# nrf51.net
KiCad netlist of a schematic drawn in Altium Designer
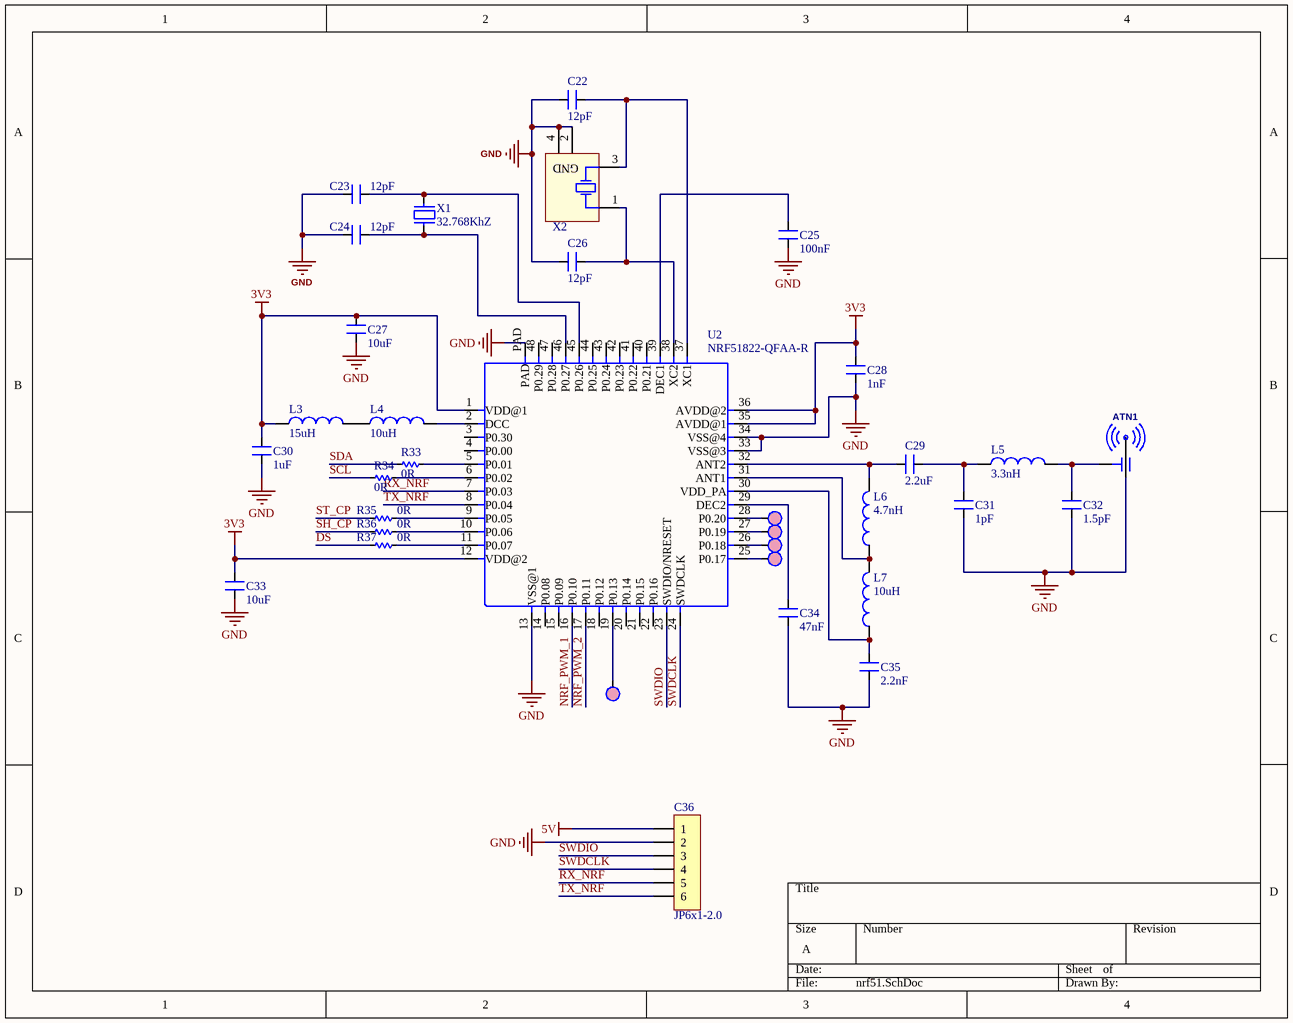
[diagram p0: nrf51.SchDoc]

(export (version "E")
  (design (tool "Eeschema 10.0.6"))
  (components
    (comp (ref "ATN1")
      (value "P-ANT")
      (footprint "Antenna 2G4")
      (libsource (lib "VitalSignal EcgPpg Board") (part "P-ANT"))
    )
    (comp (ref "C22")
      (value "12pF")
      (footprint "CN-SMD-0603")
      (description "Tu gom")
      (libsource (lib "LIBTanCN") (part "CN"))
    )
    (comp (ref "C23")
      (value "12pF")
      (footprint "CN-SMD-0603")
      (description "Tu gom")
      (libsource (lib "LIBTanCN") (part "CN"))
    )
    (comp (ref "C24")
      (value "12pF")
      (footprint "CN-SMD-0603")
      (description "Tu gom")
      (libsource (lib "LIBTanCN") (part "CN"))
    )
    (comp (ref "C25")
      (value "100nF")
      (footprint "CN-SMD-0603")
      (description "Tu gom")
      (libsource (lib "LIBTanCN") (part "CN"))
    )
    (comp (ref "C26")
      (value "12pF")
      (footprint "CN-SMD-0603")
      (description "Tu gom")
      (libsource (lib "LIBTanCN") (part "CN"))
    )
    (comp (ref "C27")
      (value "10uF")
      (footprint "CN-SMD-0603")
      (description "Tu gom")
      (libsource (lib "LIBTanCN") (part "CN"))
    )
    (comp (ref "C28")
      (value "1nF")
      (footprint "CN-SMD-0603")
      (description "Tu gom")
      (libsource (lib "LIBTanCN") (part "CN"))
    )
    (comp (ref "C29")
      (value "2.2uF")
      (footprint "CN-SMD-0603")
      (description "Tu gom")
      (libsource (lib "LIBTanCN") (part "CN"))
    )
    (comp (ref "C30")
      (value "1uF")
      (footprint "CN-SMD-0603")
      (description "Tu gom")
      (libsource (lib "LIBTanCN") (part "CN"))
    )
    (comp (ref "C31")
      (value "1pF")
      (footprint "CN-SMD-0603")
      (description "Tu gom")
      (libsource (lib "LIBTanCN") (part "CN"))
    )
    (comp (ref "C32")
      (value "1.5pF")
      (footprint "CN-SMD-0603")
      (description "Tu gom")
      (libsource (lib "LIBTanCN") (part "CN"))
    )
    (comp (ref "C33")
      (value "10uF")
      (footprint "CN-SMD-0603")
      (description "Tu gom")
      (libsource (lib "LIBTanCN") (part "CN"))
    )
    (comp (ref "C34")
      (value "47nF")
      (footprint "CN-SMD-0603")
      (description "Tu gom")
      (libsource (lib "LIBTanCN") (part "CN"))
    )
    (comp (ref "C35")
      (value "2.2nF")
      (footprint "CN-SMD-0603")
      (description "Tu gom")
      (libsource (lib "LIBTanCN") (part "CN"))
    )
    (comp (ref "C36")
      (value "JP6x1-2.0")
      (footprint "J6-C1T")
      (description "WR-PHD 2.00 mm Socket Header")
      (fields
        (field (name "MANUFACTURER") "Würth Elektronik eiSos GmbH")
        (field (name "PARTNO") "62000611821")
        (field (name "CREATED BY") "Karrer Zheng")
      )
      (libsource (lib "LIBRARY") (part "JP6x1-2.0"))
    )
    (comp (ref "L3")
      (value "15uH")
      (footprint "Inductor_0603:INDC1608X95N")
      (description "Ind Chip Shielded Multi-Layer 10uH 30% 1MHz Ferrite 50mA 0603 T/R")
      (fields (field (name "MP") "ASMCI-0603-100N-T"))
      (libsource (lib "Inductor_0603") (part "ASMCI-0603-100N-T"))
    )
    (comp (ref "L4")
      (value "10uH")
      (footprint "Inductor_0603:INDC1608X95N")
      (description "Ind Chip Shielded Multi-Layer 10uH 30% 1MHz Ferrite 50mA 0603 T/R")
      (fields (field (name "MP") "ASMCI-0603-100N-T"))
      (libsource (lib "Inductor_0603") (part "ASMCI-0603-100N-T"))
    )
    (comp (ref "L5")
      (value "3.3nH")
      (footprint "Inductor_0603:INDC1608X95N")
      (description "Ind Chip Shielded Multi-Layer 10uH 30% 1MHz Ferrite 50mA 0603 T/R")
      (fields (field (name "MP") "ASMCI-0603-100N-T"))
      (libsource (lib "Inductor_0603") (part "ASMCI-0603-100N-T"))
    )
    (comp (ref "L6")
      (value "4.7nH")
      (footprint "Inductor_0603:INDC1608X95N")
      (description "Ind Chip Shielded Multi-Layer 10uH 30% 1MHz Ferrite 50mA 0603 T/R")
      (fields (field (name "MP") "ASMCI-0603-100N-T"))
      (libsource (lib "Inductor_0603") (part "ASMCI-0603-100N-T"))
    )
    (comp (ref "L7")
      (value "10uH")
      (footprint "Inductor_0603:INDC1608X95N")
      (description "Ind Chip Shielded Multi-Layer 10uH 30% 1MHz Ferrite 50mA 0603 T/R")
      (fields (field (name "MP") "ASMCI-0603-100N-T"))
      (libsource (lib "Inductor_0603") (part "ASMCI-0603-100N-T"))
    )
    (comp (ref "R33")
      (value "0R")
      (footprint "RES-SMD-0603")
      (description "Resistor")
      (fields
        (field (name "MANUFACTURER") "Generic Components")
        (field (name "PUBLISHER") "Altium Hobart Technology Centre")
      )
      (libsource (lib "LIBRARY") (part "Res-SMD"))
    )
    (comp (ref "R34")
      (value "0R")
      (footprint "RES-SMD-0603")
      (description "Resistor")
      (fields
        (field (name "MANUFACTURER") "Generic Components")
        (field (name "PUBLISHER") "Altium Hobart Technology Centre")
      )
      (libsource (lib "LIBRARY") (part "Res-SMD"))
    )
    (comp (ref "R35")
      (value "0R")
      (footprint "RES-SMD-0603")
      (description "Resistor")
      (fields
        (field (name "MANUFACTURER") "Generic Components")
        (field (name "PUBLISHER") "Altium Hobart Technology Centre")
      )
      (libsource (lib "LIBRARY") (part "Res-SMD"))
    )
    (comp (ref "R36")
      (value "0R")
      (footprint "RES-SMD-0603")
      (description "Resistor")
      (fields
        (field (name "MANUFACTURER") "Generic Components")
        (field (name "PUBLISHER") "Altium Hobart Technology Centre")
      )
      (libsource (lib "LIBRARY") (part "Res-SMD"))
    )
    (comp (ref "R37")
      (value "0R")
      (footprint "RES-SMD-0603")
      (description "Resistor")
      (fields
        (field (name "MANUFACTURER") "Generic Components")
        (field (name "PUBLISHER") "Altium Hobart Technology Centre")
      )
      (libsource (lib "LIBRARY") (part "Res-SMD"))
    )
    (comp (ref "TP1")
      (value "TP")
      (footprint "P-TP 1MM")
      (libsource (lib "VitalSignal EcgPpg Board") (part "P-TESTPOINT"))
    )
    (comp (ref "TP2")
      (value "TP")
      (footprint "P-TP 1MM")
      (libsource (lib "VitalSignal EcgPpg Board") (part "P-TESTPOINT"))
    )
    (comp (ref "TP3")
      (value "TP")
      (footprint "P-TP 1MM")
      (libsource (lib "VitalSignal EcgPpg Board") (part "P-TESTPOINT"))
    )
    (comp (ref "TP4")
      (value "TP")
      (footprint "P-TP 1MM")
      (libsource (lib "VitalSignal EcgPpg Board") (part "P-TESTPOINT"))
    )
    (comp (ref "TP5")
      (value "TP")
      (footprint "P-TP 1MM")
      (libsource (lib "VitalSignal EcgPpg Board") (part "P-TESTPOINT"))
    )
    (comp (ref "U2")
      (value "NRF51822-QFAA-R")
      (footprint "QFN48G-0.4-6X6MM:QFN48G-0.4-6X6MM")
      (description "IC RF TxRx + MCU Bluetooth, General ISM > 1GHz Bluetooth v4.0 2.4GHz 48-VFQFN Exposed Pad")
      (fields (field (name "MF") "Nordic"))
      (libsource (lib "NRF51822-QFAA-R") (part "NRF51822-QFAA-R"))
    )
    (comp (ref "X1")
      (value "32.768KhZ")
      (footprint "XT2-32.768KHz-2_V")
      (description "Crystal, 32.768 KHz, -40 to 85 degC, 3.2 x 1.5 x 0.9 mm SMD")
      (libsource (lib "LIBRARY") (part "XT2"))
    )
    (comp (ref "X2")
      (value "XT4")
      (footprint "XT4-16.000MHz-4_V")
      (description "Crystal, 16 MHz, -30 to 85 degC, 3.2 x 2.5 x 0.9 mm SMD")
      (libsource (lib "LIBRARY") (part "XT4"))
    )
  )
  (nets
    (net (code "1") (name "/DS") (class "Default")
      (node (ref "R37") (pin "1") (pinfunction "1_1") (pintype "passive"))
    )
    (net (code "2") (name "/NRF_PWM_1") (class "Default")
      (node (ref "U2") (pin "16") (pinfunction "P0.10_16") (pintype "bidirectional"))
    )
    (net (code "3") (name "/NRF_PWM_2") (class "Default")
      (node (ref "U2") (pin "17") (pinfunction "P0.11_17") (pintype "bidirectional"))
    )
    (net (code "4") (name "/RX_NRF") (class "Default")
      (node (ref "C36") (pin "5") (pinfunction "5_5") (pintype "passive"))
      (node (ref "U2") (pin "7") (pinfunction "P0.03_7") (pintype "bidirectional"))
    )
    (net (code "5") (name "/SCL") (class "Default")
      (node (ref "R34") (pin "2") (pinfunction "2_2") (pintype "passive"))
    )
    (net (code "6") (name "/SDA") (class "Default")
      (node (ref "R33") (pin "2") (pinfunction "2_2") (pintype "passive"))
    )
    (net (code "7") (name "/SH_CP") (class "Default")
      (node (ref "R36") (pin "1") (pinfunction "1_1") (pintype "passive"))
    )
    (net (code "8") (name "/ST_CP") (class "Default")
      (node (ref "R35") (pin "1") (pinfunction "1_1") (pintype "passive"))
    )
    (net (code "9") (name "/SWDCLK") (class "Default")
      (node (ref "C36") (pin "4") (pinfunction "4_4") (pintype "passive"))
      (node (ref "U2") (pin "24") (pinfunction "SWDCLK_24") (pintype "bidirectional"))
    )
    (net (code "10") (name "/SWDIO") (class "Default")
      (node (ref "C36") (pin "3") (pinfunction "3_3") (pintype "passive"))
      (node (ref "U2") (pin "23") (pinfunction "SWDIO/NRESET_23") (pintype "bidirectional"))
    )
    (net (code "11") (name "/TX_NRF") (class "Default")
      (node (ref "C36") (pin "6") (pinfunction "6_6") (pintype "passive"))
      (node (ref "U2") (pin "8") (pinfunction "P0.04_8") (pintype "bidirectional"))
    )
    (net (code "12") (name "3V3") (class "Default")
      (node (ref "C27") (pin "1") (pinfunction "1_1") (pintype "passive"))
      (node (ref "C28") (pin "2") (pinfunction "2_2") (pintype "passive"))
      (node (ref "C30") (pin "1") (pinfunction "1_1") (pintype "passive"))
      (node (ref "C33") (pin "1") (pinfunction "1_1") (pintype "passive"))
      (node (ref "L3") (pin "1") (pinfunction "1_1") (pintype "passive"))
      (node (ref "U2") (pin "1") (pinfunction "VDD@1_1") (pintype "bidirectional"))
      (node (ref "U2") (pin "12") (pinfunction "VDD@2_12") (pintype "bidirectional"))
      (node (ref "U2") (pin "35") (pinfunction "AVDD@1_35") (pintype "bidirectional"))
      (node (ref "U2") (pin "36") (pinfunction "AVDD@2_36") (pintype "bidirectional"))
    )
    (net (code "13") (name "5V") (class "Default")
      (node (ref "C36") (pin "1") (pinfunction "1_1") (pintype "passive"))
    )
    (net (code "14") (name "GND") (class "Default")
      (node (ref "ATN1") (pin "1") (pinfunction "1_1") (pintype "passive"))
      (node (ref "C22") (pin "1") (pinfunction "1_1") (pintype "passive"))
      (node (ref "C23") (pin "2") (pinfunction "2_2") (pintype "passive"))
      (node (ref "C24") (pin "2") (pinfunction "2_2") (pintype "passive"))
      (node (ref "C25") (pin "2") (pinfunction "2_2") (pintype "passive"))
      (node (ref "C26") (pin "1") (pinfunction "1_1") (pintype "passive"))
      (node (ref "C27") (pin "2") (pinfunction "2_2") (pintype "passive"))
      (node (ref "C28") (pin "1") (pinfunction "1_1") (pintype "passive"))
      (node (ref "C30") (pin "2") (pinfunction "2_2") (pintype "passive"))
      (node (ref "C31") (pin "2") (pinfunction "2_2") (pintype "passive"))
      (node (ref "C32") (pin "2") (pinfunction "2_2") (pintype "passive"))
      (node (ref "C33") (pin "2") (pinfunction "2_2") (pintype "passive"))
      (node (ref "C34") (pin "2") (pinfunction "2_2") (pintype "passive"))
      (node (ref "C35") (pin "2") (pinfunction "2_2") (pintype "passive"))
      (node (ref "C36") (pin "2") (pinfunction "2_2") (pintype "passive"))
      (node (ref "U2") (pin "13") (pinfunction "VSS@1_13") (pintype "bidirectional"))
      (node (ref "U2") (pin "33") (pinfunction "VSS@3_33") (pintype "bidirectional"))
      (node (ref "U2") (pin "34") (pinfunction "VSS@4_34") (pintype "bidirectional"))
      (node (ref "U2") (pin "PAD") (pinfunction "PAD_PAD") (pintype "bidirectional"))
      (node (ref "X2") (pin "2") (pinfunction "GND_2") (pintype "power_in"))
      (node (ref "X2") (pin "4") (pinfunction "GND_4") (pintype "power_in"))
    )
    (net (code "15") (name "Net-(ATN1-Pad2)") (class "Default")
      (node (ref "ATN1") (pin "2") (pinfunction "2_2") (pintype "passive"))
      (node (ref "C32") (pin "1") (pinfunction "1_1") (pintype "passive"))
      (node (ref "L5") (pin "2") (pinfunction "2_2") (pintype "passive"))
    )
    (net (code "16") (name "Net-(C29-Pad1)") (class "Default")
      (node (ref "C29") (pin "1") (pinfunction "1_1") (pintype "passive"))
      (node (ref "C31") (pin "1") (pinfunction "1_1") (pintype "passive"))
      (node (ref "L5") (pin "1") (pinfunction "1_1") (pintype "passive"))
    )
    (net (code "17") (name "Net-(L3-Pad2)") (class "Default")
      (node (ref "L3") (pin "2") (pinfunction "2_2") (pintype "passive"))
      (node (ref "L4") (pin "1") (pinfunction "1_1") (pintype "passive"))
    )
    (net (code "18") (name "Net-(U2-ANT1)") (class "Default")
      (node (ref "L6") (pin "1") (pinfunction "1_1") (pintype "passive"))
      (node (ref "L7") (pin "2") (pinfunction "2_2") (pintype "passive"))
      (node (ref "U2") (pin "31") (pinfunction "ANT1_31") (pintype "bidirectional"))
    )
    (net (code "19") (name "Net-(U2-ANT2)") (class "Default")
      (node (ref "C29") (pin "2") (pinfunction "2_2") (pintype "passive"))
      (node (ref "L6") (pin "2") (pinfunction "2_2") (pintype "passive"))
      (node (ref "U2") (pin "32") (pinfunction "ANT2_32") (pintype "bidirectional"))
    )
    (net (code "20") (name "Net-(U2-DCC)") (class "Default")
      (node (ref "L4") (pin "2") (pinfunction "2_2") (pintype "passive"))
      (node (ref "U2") (pin "2") (pinfunction "DCC_2") (pintype "bidirectional"))
    )
    (net (code "21") (name "Net-(U2-DEC1)") (class "Default")
      (node (ref "C25") (pin "1") (pinfunction "1_1") (pintype "passive"))
      (node (ref "U2") (pin "39") (pinfunction "DEC1_39") (pintype "bidirectional"))
    )
    (net (code "22") (name "Net-(U2-DEC2)") (class "Default")
      (node (ref "C34") (pin "1") (pinfunction "1_1") (pintype "passive"))
      (node (ref "U2") (pin "29") (pinfunction "DEC2_29") (pintype "bidirectional"))
    )
    (net (code "23") (name "Net-(U2-P0.01)") (class "Default")
      (node (ref "R33") (pin "1") (pinfunction "1_1") (pintype "passive"))
      (node (ref "U2") (pin "5") (pinfunction "P0.01_5") (pintype "bidirectional"))
    )
    (net (code "24") (name "Net-(U2-P0.02)") (class "Default")
      (node (ref "R34") (pin "1") (pinfunction "1_1") (pintype "passive"))
      (node (ref "U2") (pin "6") (pinfunction "P0.02_6") (pintype "bidirectional"))
    )
    (net (code "25") (name "Net-(U2-P0.05)") (class "Default")
      (node (ref "R35") (pin "2") (pinfunction "2_2") (pintype "passive"))
      (node (ref "U2") (pin "9") (pinfunction "P0.05_9") (pintype "bidirectional"))
    )
    (net (code "26") (name "Net-(U2-P0.06)") (class "Default")
      (node (ref "R36") (pin "2") (pinfunction "2_2") (pintype "passive"))
      (node (ref "U2") (pin "10") (pinfunction "P0.06_10") (pintype "bidirectional"))
    )
    (net (code "27") (name "Net-(U2-P0.07)") (class "Default")
      (node (ref "R37") (pin "2") (pinfunction "2_2") (pintype "passive"))
      (node (ref "U2") (pin "11") (pinfunction "P0.07_11") (pintype "bidirectional"))
    )
    (net (code "28") (name "Net-(U2-P0.13)") (class "Default")
      (node (ref "TP5") (pin "1") (pinfunction "1_1") (pintype "passive"))
      (node (ref "U2") (pin "19") (pinfunction "P0.13_19") (pintype "bidirectional"))
    )
    (net (code "29") (name "Net-(U2-P0.17)") (class "Default")
      (node (ref "TP4") (pin "1") (pinfunction "1_1") (pintype "passive"))
      (node (ref "U2") (pin "25") (pinfunction "P0.17_25") (pintype "bidirectional"))
    )
    (net (code "30") (name "Net-(U2-P0.18)") (class "Default")
      (node (ref "TP3") (pin "1") (pinfunction "1_1") (pintype "passive"))
      (node (ref "U2") (pin "26") (pinfunction "P0.18_26") (pintype "bidirectional"))
    )
    (net (code "31") (name "Net-(U2-P0.19)") (class "Default")
      (node (ref "TP2") (pin "1") (pinfunction "1_1") (pintype "passive"))
      (node (ref "U2") (pin "27") (pinfunction "P0.19_27") (pintype "bidirectional"))
    )
    (net (code "32") (name "Net-(U2-P0.20)") (class "Default")
      (node (ref "TP1") (pin "1") (pinfunction "1_1") (pintype "passive"))
      (node (ref "U2") (pin "28") (pinfunction "P0.20_28") (pintype "bidirectional"))
    )
    (net (code "33") (name "Net-(U2-P0.26)") (class "Default")
      (node (ref "C23") (pin "1") (pinfunction "1_1") (pintype "passive"))
      (node (ref "U2") (pin "45") (pinfunction "P0.26_45") (pintype "bidirectional"))
      (node (ref "X1") (pin "2") (pinfunction "2_2") (pintype "passive"))
    )
    (net (code "34") (name "Net-(U2-P0.27)") (class "Default")
      (node (ref "C24") (pin "1") (pinfunction "1_1") (pintype "passive"))
      (node (ref "U2") (pin "46") (pinfunction "P0.27_46") (pintype "bidirectional"))
      (node (ref "X1") (pin "1") (pinfunction "1_1") (pintype "passive"))
    )
    (net (code "35") (name "Net-(U2-VDD_PA)") (class "Default")
      (node (ref "C35") (pin "1") (pinfunction "1_1") (pintype "passive"))
      (node (ref "L7") (pin "1") (pinfunction "1_1") (pintype "passive"))
      (node (ref "U2") (pin "30") (pinfunction "VDD_PA_30") (pintype "bidirectional"))
    )
    (net (code "36") (name "Net-(U2-XC1)") (class "Default")
      (node (ref "C22") (pin "2") (pinfunction "2_2") (pintype "passive"))
      (node (ref "U2") (pin "37") (pinfunction "XC1_37") (pintype "bidirectional"))
      (node (ref "X2") (pin "3") (pinfunction "XTAL_3") (pintype "passive"))
    )
    (net (code "37") (name "Net-(U2-XC2)") (class "Default")
      (node (ref "C26") (pin "2") (pinfunction "2_2") (pintype "passive"))
      (node (ref "U2") (pin "38") (pinfunction "XC2_38") (pintype "bidirectional"))
      (node (ref "X2") (pin "1") (pinfunction "XTAL_1") (pintype "passive"))
    )
    (net (code "38") (name "unconnected-(U2-P0.00-Pad4)") (class "Default")
      (node (ref "U2") (pin "4") (pinfunction "P0.00_4") (pintype "bidirectional"))
    )
    (net (code "39") (name "unconnected-(U2-P0.08-Pad14)") (class "Default")
      (node (ref "U2") (pin "14") (pinfunction "P0.08_14") (pintype "bidirectional"))
    )
    (net (code "40") (name "unconnected-(U2-P0.09-Pad15)") (class "Default")
      (node (ref "U2") (pin "15") (pinfunction "P0.09_15") (pintype "bidirectional"))
    )
    (net (code "41") (name "unconnected-(U2-P0.12-Pad18)") (class "Default")
      (node (ref "U2") (pin "18") (pinfunction "P0.12_18") (pintype "bidirectional"))
    )
    (net (code "42") (name "unconnected-(U2-P0.14-Pad20)") (class "Default")
      (node (ref "U2") (pin "20") (pinfunction "P0.14_20") (pintype "bidirectional"))
    )
    (net (code "43") (name "unconnected-(U2-P0.15-Pad21)") (class "Default")
      (node (ref "U2") (pin "21") (pinfunction "P0.15_21") (pintype "bidirectional"))
    )
    (net (code "44") (name "unconnected-(U2-P0.16-Pad22)") (class "Default")
      (node (ref "U2") (pin "22") (pinfunction "P0.16_22") (pintype "bidirectional"))
    )
    (net (code "45") (name "unconnected-(U2-P0.21-Pad40)") (class "Default")
      (node (ref "U2") (pin "40") (pinfunction "P0.21_40") (pintype "bidirectional"))
    )
    (net (code "46") (name "unconnected-(U2-P0.22-Pad41)") (class "Default")
      (node (ref "U2") (pin "41") (pinfunction "P0.22_41") (pintype "bidirectional"))
    )
    (net (code "47") (name "unconnected-(U2-P0.23-Pad42)") (class "Default")
      (node (ref "U2") (pin "42") (pinfunction "P0.23_42") (pintype "bidirectional"))
    )
    (net (code "48") (name "unconnected-(U2-P0.24-Pad43)") (class "Default")
      (node (ref "U2") (pin "43") (pinfunction "P0.24_43") (pintype "bidirectional"))
    )
    (net (code "49") (name "unconnected-(U2-P0.25-Pad44)") (class "Default")
      (node (ref "U2") (pin "44") (pinfunction "P0.25_44") (pintype "bidirectional"))
    )
    (net (code "50") (name "unconnected-(U2-P0.28-Pad47)") (class "Default")
      (node (ref "U2") (pin "47") (pinfunction "P0.28_47") (pintype "bidirectional"))
    )
    (net (code "51") (name "unconnected-(U2-P0.29-Pad48)") (class "Default")
      (node (ref "U2") (pin "48") (pinfunction "P0.29_48") (pintype "bidirectional"))
    )
    (net (code "52") (name "unconnected-(U2-P0.30-Pad3)") (class "Default")
      (node (ref "U2") (pin "3") (pinfunction "P0.30_3") (pintype "bidirectional"))
    )
  )
)
